# POWER_CONNECTOR.net
KiCad netlist of a schematic drawn in Altium Designer
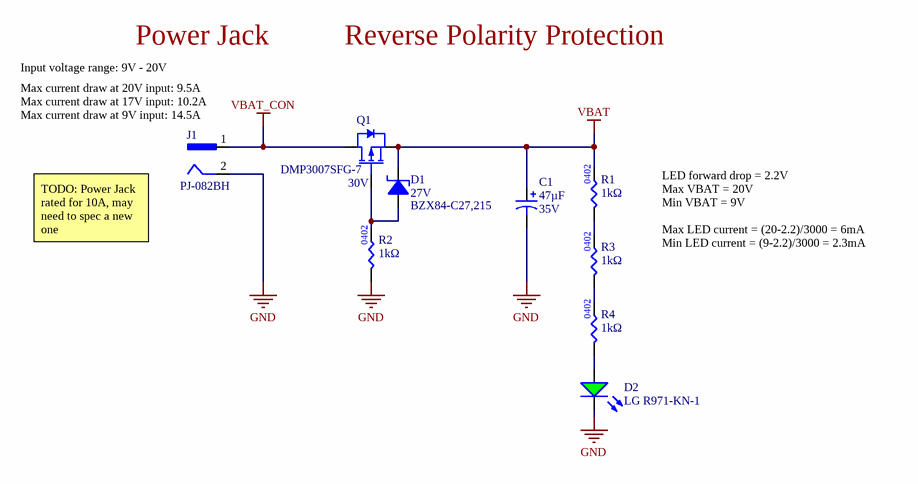
[diagram p0: POWER CONNECTOR.SchDoc]

(export (version "E")
  (design (tool "Eeschema 10.0.6"))
  (components
    (comp (ref "C1")
      (value "47µF")
      (footprint "RADIAL_CORNELL_D")
      (description "CAP ALUM POLY HYB 47UF 35V SMD")
      (fields (field (name "VOLTAGE RATING") "35V") (field (name "Comment") "CAP_47uF_35V_ALUM"))
      (libsource (lib "UWRT_Schematic_Library_2020") (part "CAP_47uF_35V_ALUM"))
    )
    (comp (ref "D1")
      (value "DIO_ZENER_27V")
      (footprint "BZX84-C27,215")
      (description "DIODE ZENER 27V 250MW SOT23")
      (fields
        (field (name "MANUFACTURER PART NUMBER 1") "BZX84-C27,215")
        (field (name "WORKING VOLTAGE") "27V")
      )
      (libsource (lib "UWRT_Schematic_Library_2020") (part "DIO_ZENER_27V"))
    )
    (comp (ref "D2")
      (value "DIO_LED_G")
      (footprint "LED_0805_GREEN")
      (description "LED GREEN DIFFUSED 0805 SMD")
      (fields (field (name "MANUFACTURER PART NUMBER 1") "LG R971-KN-1"))
      (libsource (lib "UWRT_Schematic_Library_2020") (part "DIO_LED_G"))
    )
    (comp (ref "J1")
      (value "CON_POWER_JACK")
      (footprint "CUI_PJ-082BH")
      (description "CONN PWR JACK 2.5X5.5MM SOLDER")
      (fields (field (name "MANUFACTURER PART NUMBER 1") "PJ-082BH"))
      (libsource (lib "UWRT_Schematic_Library_2020") (part "CON_POWER_JACK"))
    )
    (comp (ref "Q1")
      (value "PMOS_30V_70A")
      (footprint "DMP3007SFG-7")
      (description "MOSFET P-CH 30V 70A POWERDI3333")
      (fields (field (name "MANUFACTURER PART NUMBER 1") "DMP3007SFG-7") (field (name "VDSS") "30V"))
      (libsource (lib "UWRT_Schematic_Library_2020") (part "PMOS_30V_70A"))
    )
    (comp (ref "R1")
      (value "RES_1kΩ_0402")
      (footprint "RES0402")
      (fields
        (field (name "MANUFACTURER") "Stackpole Electronics")
        (field (name "MANUFACTURER PART NUMBER") "RMCF0402FT1K00")
        (field (name "TOLERANCE") "1%")
        (field (name "RESISTANCE") "1kΩ")
      )
      (libsource (lib "UWRT_Schematic_Library_2020") (part "RES_1kΩ_0402"))
    )
    (comp (ref "R2")
      (value "RES_1kΩ_0402")
      (footprint "RES0402")
      (fields
        (field (name "MANUFACTURER") "Stackpole Electronics")
        (field (name "MANUFACTURER PART NUMBER") "RMCF0402FT1K00")
        (field (name "TOLERANCE") "1%")
        (field (name "RESISTANCE") "1kΩ")
      )
      (libsource (lib "UWRT_Schematic_Library_2020") (part "RES_1kΩ_0402"))
    )
    (comp (ref "R3")
      (value "RES_1kΩ_0402")
      (footprint "RES0402")
      (fields
        (field (name "MANUFACTURER") "Stackpole Electronics")
        (field (name "MANUFACTURER PART NUMBER") "RMCF0402FT1K00")
        (field (name "TOLERANCE") "1%")
        (field (name "RESISTANCE") "1kΩ")
      )
      (libsource (lib "UWRT_Schematic_Library_2020") (part "RES_1kΩ_0402"))
    )
    (comp (ref "R4")
      (value "RES_1kΩ_0402")
      (footprint "RES0402")
      (fields
        (field (name "MANUFACTURER") "Stackpole Electronics")
        (field (name "MANUFACTURER PART NUMBER") "RMCF0402FT1K00")
        (field (name "TOLERANCE") "1%")
        (field (name "RESISTANCE") "1kΩ")
      )
      (libsource (lib "UWRT_Schematic_Library_2020") (part "RES_1kΩ_0402"))
    )
  )
  (nets
    (net (code "1") (name "GND") (class "Default")
      (node (ref "C1") (pin "2") (pinfunction "2_2") (pintype "passive"))
      (node (ref "D2") (pin "2") (pinfunction "K_2") (pintype "passive"))
      (node (ref "J1") (pin "2") (pinfunction "2_2") (pintype "passive"))
      (node (ref "R2") (pin "1") (pinfunction "1_1") (pintype "passive"))
    )
    (net (code "2") (name "Net-(D1-Anode)") (class "Default")
      (node (ref "D1") (pin "1") (pinfunction "Anode_1") (pintype "passive"))
      (node (ref "Q1") (pin "2") (pinfunction "Gate_2") (pintype "passive"))
      (node (ref "R2") (pin "2") (pinfunction "2_2") (pintype "passive"))
    )
    (net (code "3") (name "Net-(D2-A)") (class "Default")
      (node (ref "D2") (pin "1") (pinfunction "A_1") (pintype "passive"))
      (node (ref "R4") (pin "1") (pinfunction "1_1") (pintype "passive"))
    )
    (net (code "4") (name "Net-(R1-Pad1)") (class "Default")
      (node (ref "R1") (pin "1") (pinfunction "1_1") (pintype "passive"))
      (node (ref "R3") (pin "2") (pinfunction "2_2") (pintype "passive"))
    )
    (net (code "5") (name "Net-(R3-Pad1)") (class "Default")
      (node (ref "R3") (pin "1") (pinfunction "1_1") (pintype "passive"))
      (node (ref "R4") (pin "2") (pinfunction "2_2") (pintype "passive"))
    )
    (net (code "6") (name "VBAT") (class "Default")
      (node (ref "C1") (pin "1") (pinfunction "1_1") (pintype "passive"))
      (node (ref "D1") (pin "3") (pinfunction "Cathode_3") (pintype "passive"))
      (node (ref "Q1") (pin "3") (pinfunction "Source_3") (pintype "passive"))
      (node (ref "R1") (pin "2") (pinfunction "2_2") (pintype "passive"))
    )
    (net (code "7") (name "VBAT_CON") (class "Default")
      (node (ref "J1") (pin "1") (pinfunction "1_1") (pintype "passive"))
      (node (ref "Q1") (pin "1") (pinfunction "Drain_1") (pintype "passive"))
    )
  )
)
